# RH022_1.net
KiCad netlist of a schematic drawn in EAGLE
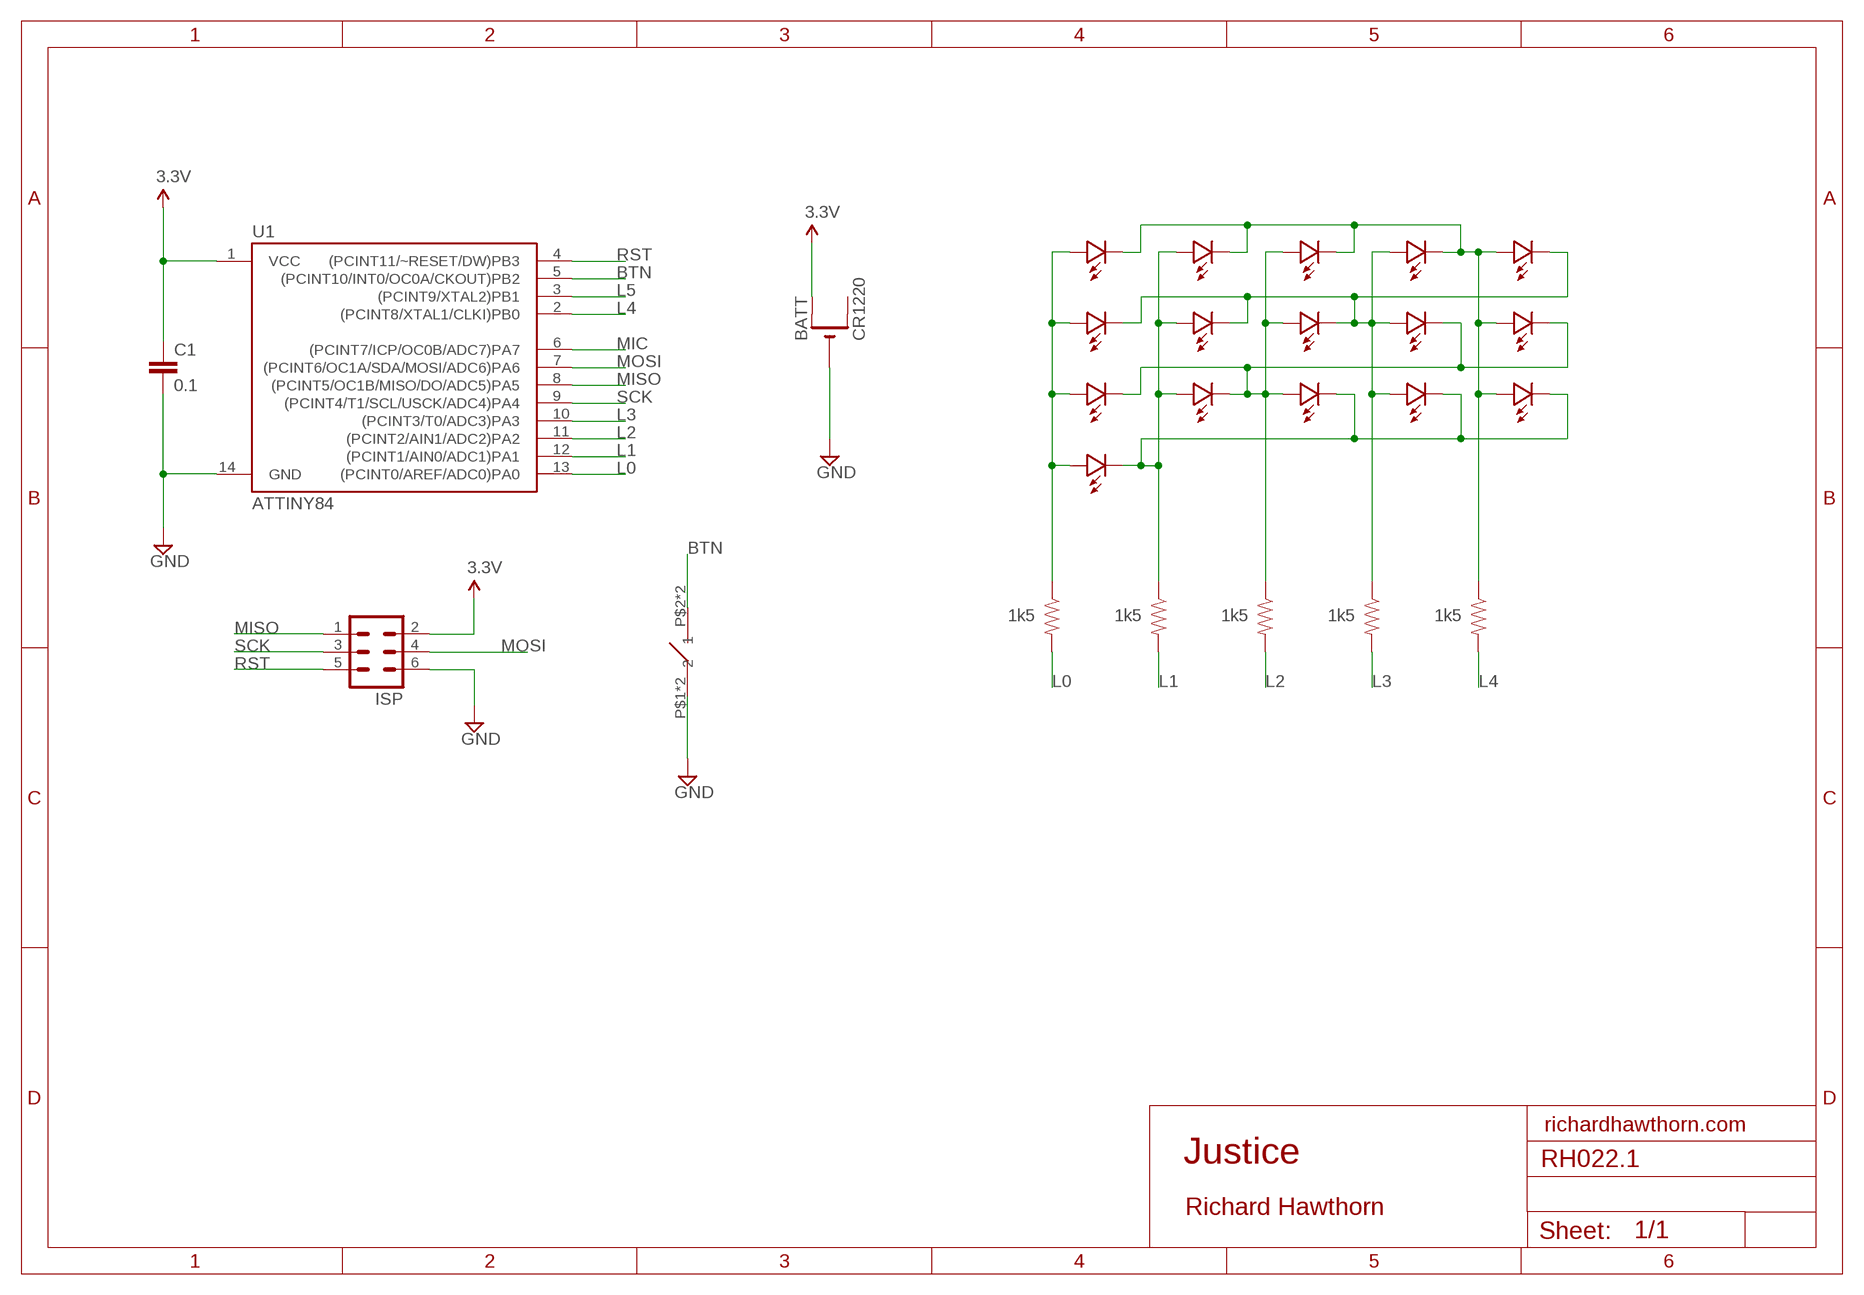
[diagram p0: schematic, sheet 1]

(export (version "E")
  (design (tool "Eeschema 10.0.6"))
  (components
    (comp (ref "BATT")
      (value "CR1220")
      (footprint "eagle-import:CR1220-SMD")
      (libsource (lib "eagle-import") (part "CR1220SMT"))
    )
    (comp (ref "BTN1")
      (value "TURTLE-3PIN")
      (footprint "eagle-import:TURTLE-3PIN")
      (libsource (lib "eagle-import") (part "TURTLE-3PIN"))
    )
    (comp (ref "C1")
      (value "0.1")
      (footprint "eagle-import:0603-CAP")
      (libsource (lib "eagle-import") (part "CAP0603-CAP"))
    )
    (comp (ref "ISP")
      (value "MA03-2")
      (footprint "eagle-import:MA03-2")
      (libsource (lib "eagle-import") (part "MA03-2"))
    )
    (comp (ref "LED1")
      (value "LED0603")
      (footprint "eagle-import:0603-LED")
      (libsource (lib "eagle-import") (part "LED0603"))
    )
    (comp (ref "LED2")
      (value "LED0603")
      (footprint "eagle-import:0603-LED")
      (libsource (lib "eagle-import") (part "LED0603"))
    )
    (comp (ref "LED3")
      (value "LED0603")
      (footprint "eagle-import:0603-LED")
      (libsource (lib "eagle-import") (part "LED0603"))
    )
    (comp (ref "LED4")
      (value "LED0603")
      (footprint "eagle-import:0603-LED")
      (libsource (lib "eagle-import") (part "LED0603"))
    )
    (comp (ref "LED5")
      (value "LED0603")
      (footprint "eagle-import:0603-LED")
      (libsource (lib "eagle-import") (part "LED0603"))
    )
    (comp (ref "LED6")
      (value "LED0603")
      (footprint "eagle-import:0603-LED")
      (libsource (lib "eagle-import") (part "LED0603"))
    )
    (comp (ref "LED7")
      (value "LED0603")
      (footprint "eagle-import:0603-LED")
      (libsource (lib "eagle-import") (part "LED0603"))
    )
    (comp (ref "LED8")
      (value "LED0603")
      (footprint "eagle-import:0603-LED")
      (libsource (lib "eagle-import") (part "LED0603"))
    )
    (comp (ref "LED9")
      (value "LED0603")
      (footprint "eagle-import:0603-LED")
      (libsource (lib "eagle-import") (part "LED0603"))
    )
    (comp (ref "LED10")
      (value "LED0603")
      (footprint "eagle-import:0603-LED")
      (libsource (lib "eagle-import") (part "LED0603"))
    )
    (comp (ref "LED11")
      (value "LED0603")
      (footprint "eagle-import:0603-LED")
      (libsource (lib "eagle-import") (part "LED0603"))
    )
    (comp (ref "LED12")
      (value "LED0603")
      (footprint "eagle-import:0603-LED")
      (libsource (lib "eagle-import") (part "LED0603"))
    )
    (comp (ref "LED13")
      (value "LED0603")
      (footprint "eagle-import:0603-LED")
      (libsource (lib "eagle-import") (part "LED0603"))
    )
    (comp (ref "LED14")
      (value "LED0603")
      (footprint "eagle-import:0603-LED")
      (libsource (lib "eagle-import") (part "LED0603"))
    )
    (comp (ref "LED15")
      (value "LED0603")
      (footprint "eagle-import:0603-LED")
      (libsource (lib "eagle-import") (part "LED0603"))
    )
    (comp (ref "LED16")
      (value "LED0603")
      (footprint "eagle-import:0603-LED")
      (libsource (lib "eagle-import") (part "LED0603"))
    )
    (comp (ref "R1")
      (value "1k5")
      (footprint "eagle-import:0603-RES")
      (libsource (lib "eagle-import") (part "RESISTOR0603-RES"))
    )
    (comp (ref "R2")
      (value "1k5")
      (footprint "eagle-import:0603-RES")
      (libsource (lib "eagle-import") (part "RESISTOR0603-RES"))
    )
    (comp (ref "R3")
      (value "1k5")
      (footprint "eagle-import:0603-RES")
      (libsource (lib "eagle-import") (part "RESISTOR0603-RES"))
    )
    (comp (ref "R4")
      (value "1k5")
      (footprint "eagle-import:0603-RES")
      (libsource (lib "eagle-import") (part "RESISTOR0603-RES"))
    )
    (comp (ref "R5")
      (value "1k5")
      (footprint "eagle-import:0603-RES")
      (libsource (lib "eagle-import") (part "RESISTOR0603-RES"))
    )
    (comp (ref "U1")
      (value "ATTINY84")
      (footprint "eagle-import:SO14")
      (libsource (lib "eagle-import") (part "ATTINY84"))
    )
  )
  (nets
    (net (code "1") (name "/BTN") (class "Default")
      (node (ref "BTN1") (pin "P$2") (pinfunction "2_P$2") (pintype "bidirectional"))
      (node (ref "BTN1") (pin "P$4") (pinfunction "2_P$4") (pintype "bidirectional"))
      (node (ref "U1") (pin "5") (pinfunction "(PCINT10/INT0/OC0A/CKOUT)PB2_5") (pintype "bidirectional"))
    )
    (net (code "2") (name "/L0") (class "Default")
      (node (ref "R1") (pin "2") (pinfunction "2_2") (pintype "passive"))
      (node (ref "U1") (pin "13") (pinfunction "(PCINT0/AREF/ADC0)PA0_13") (pintype "bidirectional"))
    )
    (net (code "3") (name "/L1") (class "Default")
      (node (ref "R2") (pin "2") (pinfunction "2_2") (pintype "passive"))
      (node (ref "U1") (pin "12") (pinfunction "(PCINT1/AIN0/ADC1)PA1_12") (pintype "bidirectional"))
    )
    (net (code "4") (name "/L2") (class "Default")
      (node (ref "R3") (pin "2") (pinfunction "2_2") (pintype "passive"))
      (node (ref "U1") (pin "11") (pinfunction "(PCINT2/AIN1/ADC2)PA2_11") (pintype "bidirectional"))
    )
    (net (code "5") (name "/L3") (class "Default")
      (node (ref "R4") (pin "2") (pinfunction "2_2") (pintype "passive"))
      (node (ref "U1") (pin "10") (pinfunction "(PCINT3/T0/ADC3)PA3_10") (pintype "bidirectional"))
    )
    (net (code "6") (name "/L4") (class "Default")
      (node (ref "R5") (pin "2") (pinfunction "2_2") (pintype "passive"))
      (node (ref "U1") (pin "2") (pinfunction "(PCINT8/XTAL1/CLKI)PB0_2") (pintype "bidirectional"))
    )
    (net (code "7") (name "/L5") (class "Default")
      (node (ref "U1") (pin "3") (pinfunction "(PCINT9/XTAL2)PB1_3") (pintype "bidirectional"))
    )
    (net (code "8") (name "/MIC") (class "Default")
      (node (ref "U1") (pin "6") (pinfunction "(PCINT7/ICP/OC0B/ADC7)PA7_6") (pintype "bidirectional"))
    )
    (net (code "9") (name "/MISO") (class "Default")
      (node (ref "ISP") (pin "1") (pinfunction "1_1") (pintype "passive"))
      (node (ref "U1") (pin "8") (pinfunction "(PCINT5/OC1B/MISO/DO/ADC5)PA5_8") (pintype "bidirectional"))
    )
    (net (code "10") (name "/MOSI") (class "Default")
      (node (ref "ISP") (pin "4") (pinfunction "4_4") (pintype "passive"))
      (node (ref "U1") (pin "7") (pinfunction "(PCINT6/OC1A/SDA/MOSI/ADC6)PA6_7") (pintype "bidirectional"))
    )
    (net (code "11") (name "/RST") (class "Default")
      (node (ref "ISP") (pin "5") (pinfunction "5_5") (pintype "passive"))
      (node (ref "U1") (pin "4") (pinfunction "(PCINT11/~{RESET/DW})PB3_4") (pintype "bidirectional"))
    )
    (net (code "12") (name "/SCK") (class "Default")
      (node (ref "ISP") (pin "3") (pinfunction "3_3") (pintype "passive"))
      (node (ref "U1") (pin "9") (pinfunction "(PCINT4/T1/SCL/USCK/ADC4)PA4_9") (pintype "bidirectional"))
    )
    (net (code "13") (name "3.3V") (class "Default")
      (node (ref "BATT") (pin "+$1") (pinfunction "+_+$1") (pintype "passive"))
      (node (ref "C1") (pin "1") (pinfunction "1_1") (pintype "passive"))
      (node (ref "ISP") (pin "2") (pinfunction "2_2") (pintype "passive"))
      (node (ref "U1") (pin "1") (pinfunction "VCC_1") (pintype "bidirectional"))
    )
    (net (code "14") (name "GND") (class "Default")
      (node (ref "BATT") (pin "-") (pinfunction "-_-") (pintype "passive"))
      (node (ref "BTN1") (pin "P$1") (pinfunction "1_P$1") (pintype "bidirectional"))
      (node (ref "BTN1") (pin "P$3") (pinfunction "1_P$3") (pintype "bidirectional"))
      (node (ref "C1") (pin "2") (pinfunction "2_2") (pintype "passive"))
      (node (ref "ISP") (pin "6") (pinfunction "6_6") (pintype "passive"))
      (node (ref "U1") (pin "14") (pinfunction "GND_14") (pintype "bidirectional"))
    )
    (net (code "15") (name "Net-(LED1-PadMINUS)") (class "Default")
      (node (ref "LED1") (pin "MINUS") (pinfunction "MINUS_MINUS") (pintype "passive"))
      (node (ref "LED10") (pin "PLUS") (pinfunction "PLUS_PLUS") (pintype "passive"))
      (node (ref "LED15") (pin "PLUS") (pinfunction "PLUS_PLUS") (pintype "passive"))
      (node (ref "LED2") (pin "MINUS") (pinfunction "MINUS_MINUS") (pintype "passive"))
      (node (ref "LED3") (pin "MINUS") (pinfunction "MINUS_MINUS") (pintype "passive"))
      (node (ref "LED4") (pin "MINUS") (pinfunction "MINUS_MINUS") (pintype "passive"))
      (node (ref "LED5") (pin "PLUS") (pinfunction "PLUS_PLUS") (pintype "passive"))
      (node (ref "R5") (pin "1") (pinfunction "1_1") (pintype "passive"))
    )
    (net (code "16") (name "Net-(LED1-PadPLUS)") (class "Default")
      (node (ref "LED1") (pin "PLUS") (pinfunction "PLUS_PLUS") (pintype "passive"))
      (node (ref "LED11") (pin "PLUS") (pinfunction "PLUS_PLUS") (pintype "passive"))
      (node (ref "LED16") (pin "PLUS") (pinfunction "PLUS_PLUS") (pintype "passive"))
      (node (ref "LED6") (pin "PLUS") (pinfunction "PLUS_PLUS") (pintype "passive"))
      (node (ref "R1") (pin "1") (pinfunction "1_1") (pintype "passive"))
    )
    (net (code "17") (name "Net-(LED10-PadMINUS)") (class "Default")
      (node (ref "LED10") (pin "MINUS") (pinfunction "MINUS_MINUS") (pintype "passive"))
      (node (ref "LED11") (pin "MINUS") (pinfunction "MINUS_MINUS") (pintype "passive"))
      (node (ref "LED12") (pin "MINUS") (pinfunction "MINUS_MINUS") (pintype "passive"))
      (node (ref "LED13") (pin "PLUS") (pinfunction "PLUS_PLUS") (pintype "passive"))
      (node (ref "LED3") (pin "PLUS") (pinfunction "PLUS_PLUS") (pintype "passive"))
      (node (ref "LED8") (pin "PLUS") (pinfunction "PLUS_PLUS") (pintype "passive"))
      (node (ref "LED9") (pin "MINUS") (pinfunction "MINUS_MINUS") (pintype "passive"))
      (node (ref "R3") (pin "1") (pinfunction "1_1") (pintype "passive"))
    )
    (net (code "18") (name "Net-(LED12-PadPLUS)") (class "Default")
      (node (ref "LED12") (pin "PLUS") (pinfunction "PLUS_PLUS") (pintype "passive"))
      (node (ref "LED13") (pin "MINUS") (pinfunction "MINUS_MINUS") (pintype "passive"))
      (node (ref "LED14") (pin "MINUS") (pinfunction "MINUS_MINUS") (pintype "passive"))
      (node (ref "LED15") (pin "MINUS") (pinfunction "MINUS_MINUS") (pintype "passive"))
      (node (ref "LED16") (pin "MINUS") (pinfunction "MINUS_MINUS") (pintype "passive"))
      (node (ref "LED2") (pin "PLUS") (pinfunction "PLUS_PLUS") (pintype "passive"))
      (node (ref "LED7") (pin "PLUS") (pinfunction "PLUS_PLUS") (pintype "passive"))
      (node (ref "R2") (pin "1") (pinfunction "1_1") (pintype "passive"))
    )
    (net (code "19") (name "Net-(LED14-PadPLUS)") (class "Default")
      (node (ref "LED14") (pin "PLUS") (pinfunction "PLUS_PLUS") (pintype "passive"))
      (node (ref "LED4") (pin "PLUS") (pinfunction "PLUS_PLUS") (pintype "passive"))
      (node (ref "LED5") (pin "MINUS") (pinfunction "MINUS_MINUS") (pintype "passive"))
      (node (ref "LED6") (pin "MINUS") (pinfunction "MINUS_MINUS") (pintype "passive"))
      (node (ref "LED7") (pin "MINUS") (pinfunction "MINUS_MINUS") (pintype "passive"))
      (node (ref "LED8") (pin "MINUS") (pinfunction "MINUS_MINUS") (pintype "passive"))
      (node (ref "LED9") (pin "PLUS") (pinfunction "PLUS_PLUS") (pintype "passive"))
      (node (ref "R4") (pin "1") (pinfunction "1_1") (pintype "passive"))
    )
    (net (code "20") (name "unconnected-(BATT-+1-Pad+$2)") (class "Default")
      (node (ref "BATT") (pin "+$2") (pinfunction "+1_+$2") (pintype "passive"))
    )
  )
)
